# devkeys.net
KiCad netlist of a schematic drawn in EAGLE
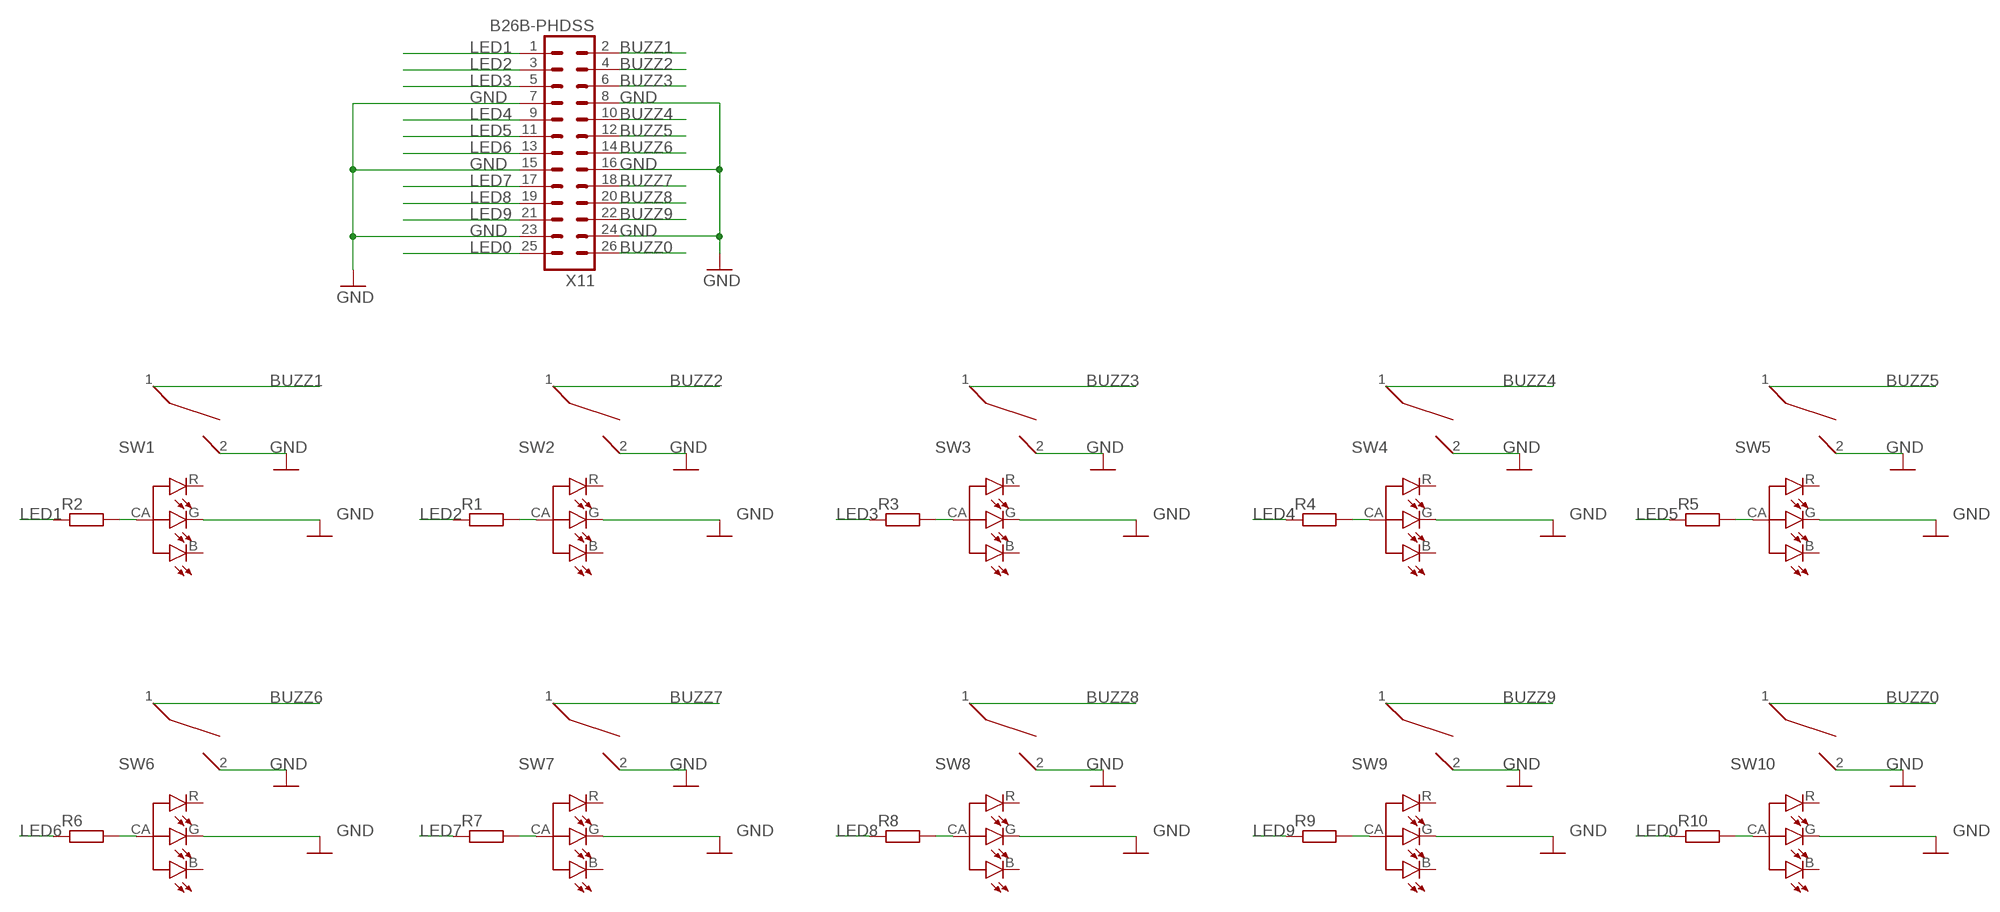
[diagram p0: schematic, sheet 1]

(export (version "E")
  (design (tool "Eeschema 10.0.6"))
  (components
    (comp (ref "R1")
      (value "R-EU_R0805")
      (footprint "eagle-import:R0805")
      (libsource (lib "eagle-import") (part "R-EU_R0805"))
    )
    (comp (ref "R2")
      (value "R-EU_R0805")
      (footprint "eagle-import:R0805")
      (libsource (lib "eagle-import") (part "R-EU_R0805"))
    )
    (comp (ref "R3")
      (value "R-EU_R0805")
      (footprint "eagle-import:R0805")
      (libsource (lib "eagle-import") (part "R-EU_R0805"))
    )
    (comp (ref "R4")
      (value "R-EU_R0805")
      (footprint "eagle-import:R0805")
      (libsource (lib "eagle-import") (part "R-EU_R0805"))
    )
    (comp (ref "R5")
      (value "R-EU_R0805")
      (footprint "eagle-import:R0805")
      (libsource (lib "eagle-import") (part "R-EU_R0805"))
    )
    (comp (ref "R6")
      (value "R-EU_R0805")
      (footprint "eagle-import:R0805")
      (libsource (lib "eagle-import") (part "R-EU_R0805"))
    )
    (comp (ref "R7")
      (value "R-EU_R0805")
      (footprint "eagle-import:R0805")
      (libsource (lib "eagle-import") (part "R-EU_R0805"))
    )
    (comp (ref "R8")
      (value "R-EU_R0805")
      (footprint "eagle-import:R0805")
      (libsource (lib "eagle-import") (part "R-EU_R0805"))
    )
    (comp (ref "R9")
      (value "R-EU_R0805")
      (footprint "eagle-import:R0805")
      (libsource (lib "eagle-import") (part "R-EU_R0805"))
    )
    (comp (ref "R10")
      (value "R-EU_R0805")
      (footprint "eagle-import:R0805")
      (libsource (lib "eagle-import") (part "R-EU_R0805"))
    )
    (comp (ref "SW1")
      (value "ZEALIOS")
      (footprint "eagle-import:ZEALIOS-PCB_1U")
      (libsource (lib "eagle-import") (part "ZEALIOS"))
    )
    (comp (ref "SW2")
      (value "ZEALIOS")
      (footprint "eagle-import:ZEALIOS-PCB_1U")
      (libsource (lib "eagle-import") (part "ZEALIOS"))
    )
    (comp (ref "SW3")
      (value "ZEALIOS")
      (footprint "eagle-import:ZEALIOS-PCB_1U")
      (libsource (lib "eagle-import") (part "ZEALIOS"))
    )
    (comp (ref "SW4")
      (value "ZEALIOS")
      (footprint "eagle-import:ZEALIOS-PCB_1U")
      (libsource (lib "eagle-import") (part "ZEALIOS"))
    )
    (comp (ref "SW5")
      (value "ZEALIOS")
      (footprint "eagle-import:ZEALIOS-PCB_1U")
      (libsource (lib "eagle-import") (part "ZEALIOS"))
    )
    (comp (ref "SW6")
      (value "ZEALIOS")
      (footprint "eagle-import:ZEALIOS-PCB_1U")
      (libsource (lib "eagle-import") (part "ZEALIOS"))
    )
    (comp (ref "SW7")
      (value "ZEALIOS")
      (footprint "eagle-import:ZEALIOS-PCB_1U")
      (libsource (lib "eagle-import") (part "ZEALIOS"))
    )
    (comp (ref "SW8")
      (value "ZEALIOS")
      (footprint "eagle-import:ZEALIOS-PCB_1U")
      (libsource (lib "eagle-import") (part "ZEALIOS"))
    )
    (comp (ref "SW9")
      (value "ZEALIOS")
      (footprint "eagle-import:ZEALIOS-PCB_1U")
      (libsource (lib "eagle-import") (part "ZEALIOS"))
    )
    (comp (ref "SW10")
      (value "ZEALIOS")
      (footprint "eagle-import:ZEALIOS-PCB_1U")
      (libsource (lib "eagle-import") (part "ZEALIOS"))
    )
    (comp (ref "X11")
      (value "B26B-PHDSS")
      (footprint "eagle-import:B26B-PHDSS")
      (libsource (lib "eagle-import") (part "B26B-PHDSS"))
    )
  )
  (nets
    (net (code "1") (name "/BUZZ0") (class "Default")
      (node (ref "SW10") (pin "1") (pinfunction "1_1") (pintype "passive"))
      (node (ref "X11") (pin "26") (pinfunction "26_26") (pintype "passive"))
    )
    (net (code "2") (name "/BUZZ1") (class "Default")
      (node (ref "SW1") (pin "1") (pinfunction "1_1") (pintype "passive"))
      (node (ref "X11") (pin "2") (pinfunction "2_2") (pintype "passive"))
    )
    (net (code "3") (name "/BUZZ2") (class "Default")
      (node (ref "SW2") (pin "1") (pinfunction "1_1") (pintype "passive"))
      (node (ref "X11") (pin "4") (pinfunction "4_4") (pintype "passive"))
    )
    (net (code "4") (name "/BUZZ3") (class "Default")
      (node (ref "SW3") (pin "1") (pinfunction "1_1") (pintype "passive"))
      (node (ref "X11") (pin "6") (pinfunction "6_6") (pintype "passive"))
    )
    (net (code "5") (name "/BUZZ4") (class "Default")
      (node (ref "SW4") (pin "1") (pinfunction "1_1") (pintype "passive"))
      (node (ref "X11") (pin "10") (pinfunction "10_10") (pintype "passive"))
    )
    (net (code "6") (name "/BUZZ5") (class "Default")
      (node (ref "SW5") (pin "1") (pinfunction "1_1") (pintype "passive"))
      (node (ref "X11") (pin "12") (pinfunction "12_12") (pintype "passive"))
    )
    (net (code "7") (name "/BUZZ6") (class "Default")
      (node (ref "SW6") (pin "1") (pinfunction "1_1") (pintype "passive"))
      (node (ref "X11") (pin "14") (pinfunction "14_14") (pintype "passive"))
    )
    (net (code "8") (name "/BUZZ7") (class "Default")
      (node (ref "SW7") (pin "1") (pinfunction "1_1") (pintype "passive"))
      (node (ref "X11") (pin "18") (pinfunction "18_18") (pintype "passive"))
    )
    (net (code "9") (name "/BUZZ8") (class "Default")
      (node (ref "SW8") (pin "1") (pinfunction "1_1") (pintype "passive"))
      (node (ref "X11") (pin "20") (pinfunction "20_20") (pintype "passive"))
    )
    (net (code "10") (name "/BUZZ9") (class "Default")
      (node (ref "SW9") (pin "1") (pinfunction "1_1") (pintype "passive"))
      (node (ref "X11") (pin "22") (pinfunction "22_22") (pintype "passive"))
    )
    (net (code "11") (name "/LED0") (class "Default")
      (node (ref "R10") (pin "1") (pinfunction "1_1") (pintype "passive"))
      (node (ref "X11") (pin "25") (pinfunction "25_25") (pintype "passive"))
    )
    (net (code "12") (name "/LED1") (class "Default")
      (node (ref "R2") (pin "1") (pinfunction "1_1") (pintype "passive"))
      (node (ref "X11") (pin "1") (pinfunction "1_1") (pintype "passive"))
    )
    (net (code "13") (name "/LED2") (class "Default")
      (node (ref "R1") (pin "1") (pinfunction "1_1") (pintype "passive"))
      (node (ref "X11") (pin "3") (pinfunction "3_3") (pintype "passive"))
    )
    (net (code "14") (name "/LED3") (class "Default")
      (node (ref "R3") (pin "1") (pinfunction "1_1") (pintype "passive"))
      (node (ref "X11") (pin "5") (pinfunction "5_5") (pintype "passive"))
    )
    (net (code "15") (name "/LED4") (class "Default")
      (node (ref "R4") (pin "1") (pinfunction "1_1") (pintype "passive"))
      (node (ref "X11") (pin "9") (pinfunction "9_9") (pintype "passive"))
    )
    (net (code "16") (name "/LED5") (class "Default")
      (node (ref "R5") (pin "1") (pinfunction "1_1") (pintype "passive"))
      (node (ref "X11") (pin "11") (pinfunction "11_11") (pintype "passive"))
    )
    (net (code "17") (name "/LED6") (class "Default")
      (node (ref "R6") (pin "1") (pinfunction "1_1") (pintype "passive"))
      (node (ref "X11") (pin "13") (pinfunction "13_13") (pintype "passive"))
    )
    (net (code "18") (name "/LED7") (class "Default")
      (node (ref "R7") (pin "1") (pinfunction "1_1") (pintype "passive"))
      (node (ref "X11") (pin "17") (pinfunction "17_17") (pintype "passive"))
    )
    (net (code "19") (name "/LED8") (class "Default")
      (node (ref "R8") (pin "1") (pinfunction "1_1") (pintype "passive"))
      (node (ref "X11") (pin "19") (pinfunction "19_19") (pintype "passive"))
    )
    (net (code "20") (name "/LED9") (class "Default")
      (node (ref "R9") (pin "1") (pinfunction "1_1") (pintype "passive"))
      (node (ref "X11") (pin "21") (pinfunction "21_21") (pintype "passive"))
    )
    (net (code "21") (name "GND") (class "Default")
      (node (ref "SW1") (pin "2") (pinfunction "2_2") (pintype "passive"))
      (node (ref "SW1") (pin "G") (pinfunction "G-CAT_G") (pintype "passive"))
      (node (ref "SW10") (pin "2") (pinfunction "2_2") (pintype "passive"))
      (node (ref "SW10") (pin "G") (pinfunction "G-CAT_G") (pintype "passive"))
      (node (ref "SW2") (pin "2") (pinfunction "2_2") (pintype "passive"))
      (node (ref "SW2") (pin "G") (pinfunction "G-CAT_G") (pintype "passive"))
      (node (ref "SW3") (pin "2") (pinfunction "2_2") (pintype "passive"))
      (node (ref "SW3") (pin "G") (pinfunction "G-CAT_G") (pintype "passive"))
      (node (ref "SW4") (pin "2") (pinfunction "2_2") (pintype "passive"))
      (node (ref "SW4") (pin "G") (pinfunction "G-CAT_G") (pintype "passive"))
      (node (ref "SW5") (pin "2") (pinfunction "2_2") (pintype "passive"))
      (node (ref "SW5") (pin "G") (pinfunction "G-CAT_G") (pintype "passive"))
      (node (ref "SW6") (pin "2") (pinfunction "2_2") (pintype "passive"))
      (node (ref "SW6") (pin "G") (pinfunction "G-CAT_G") (pintype "passive"))
      (node (ref "SW7") (pin "2") (pinfunction "2_2") (pintype "passive"))
      (node (ref "SW7") (pin "G") (pinfunction "G-CAT_G") (pintype "passive"))
      (node (ref "SW8") (pin "2") (pinfunction "2_2") (pintype "passive"))
      (node (ref "SW8") (pin "G") (pinfunction "G-CAT_G") (pintype "passive"))
      (node (ref "SW9") (pin "2") (pinfunction "2_2") (pintype "passive"))
      (node (ref "SW9") (pin "G") (pinfunction "G-CAT_G") (pintype "passive"))
      (node (ref "X11") (pin "15") (pinfunction "15_15") (pintype "passive"))
      (node (ref "X11") (pin "16") (pinfunction "16_16") (pintype "passive"))
      (node (ref "X11") (pin "23") (pinfunction "23_23") (pintype "passive"))
      (node (ref "X11") (pin "24") (pinfunction "24_24") (pintype "passive"))
      (node (ref "X11") (pin "7") (pinfunction "7_7") (pintype "passive"))
      (node (ref "X11") (pin "8") (pinfunction "8_8") (pintype "passive"))
    )
    (net (code "22") (name "Net-(SW1-COMMON-ANODE)") (class "Default")
      (node (ref "R2") (pin "2") (pinfunction "2_2") (pintype "passive"))
      (node (ref "SW1") (pin "CA") (pinfunction "COMMON-ANODE_CA") (pintype "passive"))
    )
    (net (code "23") (name "Net-(SW2-COMMON-ANODE)") (class "Default")
      (node (ref "R1") (pin "2") (pinfunction "2_2") (pintype "passive"))
      (node (ref "SW2") (pin "CA") (pinfunction "COMMON-ANODE_CA") (pintype "passive"))
    )
    (net (code "24") (name "Net-(SW3-COMMON-ANODE)") (class "Default")
      (node (ref "R3") (pin "2") (pinfunction "2_2") (pintype "passive"))
      (node (ref "SW3") (pin "CA") (pinfunction "COMMON-ANODE_CA") (pintype "passive"))
    )
    (net (code "25") (name "Net-(SW4-COMMON-ANODE)") (class "Default")
      (node (ref "R4") (pin "2") (pinfunction "2_2") (pintype "passive"))
      (node (ref "SW4") (pin "CA") (pinfunction "COMMON-ANODE_CA") (pintype "passive"))
    )
    (net (code "26") (name "Net-(SW5-COMMON-ANODE)") (class "Default")
      (node (ref "R5") (pin "2") (pinfunction "2_2") (pintype "passive"))
      (node (ref "SW5") (pin "CA") (pinfunction "COMMON-ANODE_CA") (pintype "passive"))
    )
    (net (code "27") (name "Net-(SW6-COMMON-ANODE)") (class "Default")
      (node (ref "R6") (pin "2") (pinfunction "2_2") (pintype "passive"))
      (node (ref "SW6") (pin "CA") (pinfunction "COMMON-ANODE_CA") (pintype "passive"))
    )
    (net (code "28") (name "Net-(SW7-COMMON-ANODE)") (class "Default")
      (node (ref "R7") (pin "2") (pinfunction "2_2") (pintype "passive"))
      (node (ref "SW7") (pin "CA") (pinfunction "COMMON-ANODE_CA") (pintype "passive"))
    )
    (net (code "29") (name "Net-(SW8-COMMON-ANODE)") (class "Default")
      (node (ref "R8") (pin "2") (pinfunction "2_2") (pintype "passive"))
      (node (ref "SW8") (pin "CA") (pinfunction "COMMON-ANODE_CA") (pintype "passive"))
    )
    (net (code "30") (name "Net-(SW9-COMMON-ANODE)") (class "Default")
      (node (ref "R9") (pin "2") (pinfunction "2_2") (pintype "passive"))
      (node (ref "SW9") (pin "CA") (pinfunction "COMMON-ANODE_CA") (pintype "passive"))
    )
    (net (code "31") (name "Net-(SW10-COMMON-ANODE)") (class "Default")
      (node (ref "R10") (pin "2") (pinfunction "2_2") (pintype "passive"))
      (node (ref "SW10") (pin "CA") (pinfunction "COMMON-ANODE_CA") (pintype "passive"))
    )
    (net (code "32") (name "unconnected-(SW1-B-CAT-PadB)") (class "Default")
      (node (ref "SW1") (pin "B") (pinfunction "B-CAT_B") (pintype "passive"))
    )
    (net (code "33") (name "unconnected-(SW1-R-CAT-PadR)") (class "Default")
      (node (ref "SW1") (pin "R") (pinfunction "R-CAT_R") (pintype "passive"))
    )
    (net (code "34") (name "unconnected-(SW2-B-CAT-PadB)") (class "Default")
      (node (ref "SW2") (pin "B") (pinfunction "B-CAT_B") (pintype "passive"))
    )
    (net (code "35") (name "unconnected-(SW2-R-CAT-PadR)") (class "Default")
      (node (ref "SW2") (pin "R") (pinfunction "R-CAT_R") (pintype "passive"))
    )
    (net (code "36") (name "unconnected-(SW3-B-CAT-PadB)") (class "Default")
      (node (ref "SW3") (pin "B") (pinfunction "B-CAT_B") (pintype "passive"))
    )
    (net (code "37") (name "unconnected-(SW3-R-CAT-PadR)") (class "Default")
      (node (ref "SW3") (pin "R") (pinfunction "R-CAT_R") (pintype "passive"))
    )
    (net (code "38") (name "unconnected-(SW4-B-CAT-PadB)") (class "Default")
      (node (ref "SW4") (pin "B") (pinfunction "B-CAT_B") (pintype "passive"))
    )
    (net (code "39") (name "unconnected-(SW4-R-CAT-PadR)") (class "Default")
      (node (ref "SW4") (pin "R") (pinfunction "R-CAT_R") (pintype "passive"))
    )
    (net (code "40") (name "unconnected-(SW5-B-CAT-PadB)") (class "Default")
      (node (ref "SW5") (pin "B") (pinfunction "B-CAT_B") (pintype "passive"))
    )
    (net (code "41") (name "unconnected-(SW5-R-CAT-PadR)") (class "Default")
      (node (ref "SW5") (pin "R") (pinfunction "R-CAT_R") (pintype "passive"))
    )
    (net (code "42") (name "unconnected-(SW6-B-CAT-PadB)") (class "Default")
      (node (ref "SW6") (pin "B") (pinfunction "B-CAT_B") (pintype "passive"))
    )
    (net (code "43") (name "unconnected-(SW6-R-CAT-PadR)") (class "Default")
      (node (ref "SW6") (pin "R") (pinfunction "R-CAT_R") (pintype "passive"))
    )
    (net (code "44") (name "unconnected-(SW7-B-CAT-PadB)") (class "Default")
      (node (ref "SW7") (pin "B") (pinfunction "B-CAT_B") (pintype "passive"))
    )
    (net (code "45") (name "unconnected-(SW7-R-CAT-PadR)") (class "Default")
      (node (ref "SW7") (pin "R") (pinfunction "R-CAT_R") (pintype "passive"))
    )
    (net (code "46") (name "unconnected-(SW8-B-CAT-PadB)") (class "Default")
      (node (ref "SW8") (pin "B") (pinfunction "B-CAT_B") (pintype "passive"))
    )
    (net (code "47") (name "unconnected-(SW8-R-CAT-PadR)") (class "Default")
      (node (ref "SW8") (pin "R") (pinfunction "R-CAT_R") (pintype "passive"))
    )
    (net (code "48") (name "unconnected-(SW9-B-CAT-PadB)") (class "Default")
      (node (ref "SW9") (pin "B") (pinfunction "B-CAT_B") (pintype "passive"))
    )
    (net (code "49") (name "unconnected-(SW9-R-CAT-PadR)") (class "Default")
      (node (ref "SW9") (pin "R") (pinfunction "R-CAT_R") (pintype "passive"))
    )
    (net (code "50") (name "unconnected-(SW10-B-CAT-PadB)") (class "Default")
      (node (ref "SW10") (pin "B") (pinfunction "B-CAT_B") (pintype "passive"))
    )
    (net (code "51") (name "unconnected-(SW10-R-CAT-PadR)") (class "Default")
      (node (ref "SW10") (pin "R") (pinfunction "R-CAT_R") (pintype "passive"))
    )
  )
)
